# Attiny_Sumo_2020-05-22_18-39-58.net
KiCad netlist of a schematic drawn in EasyEDA
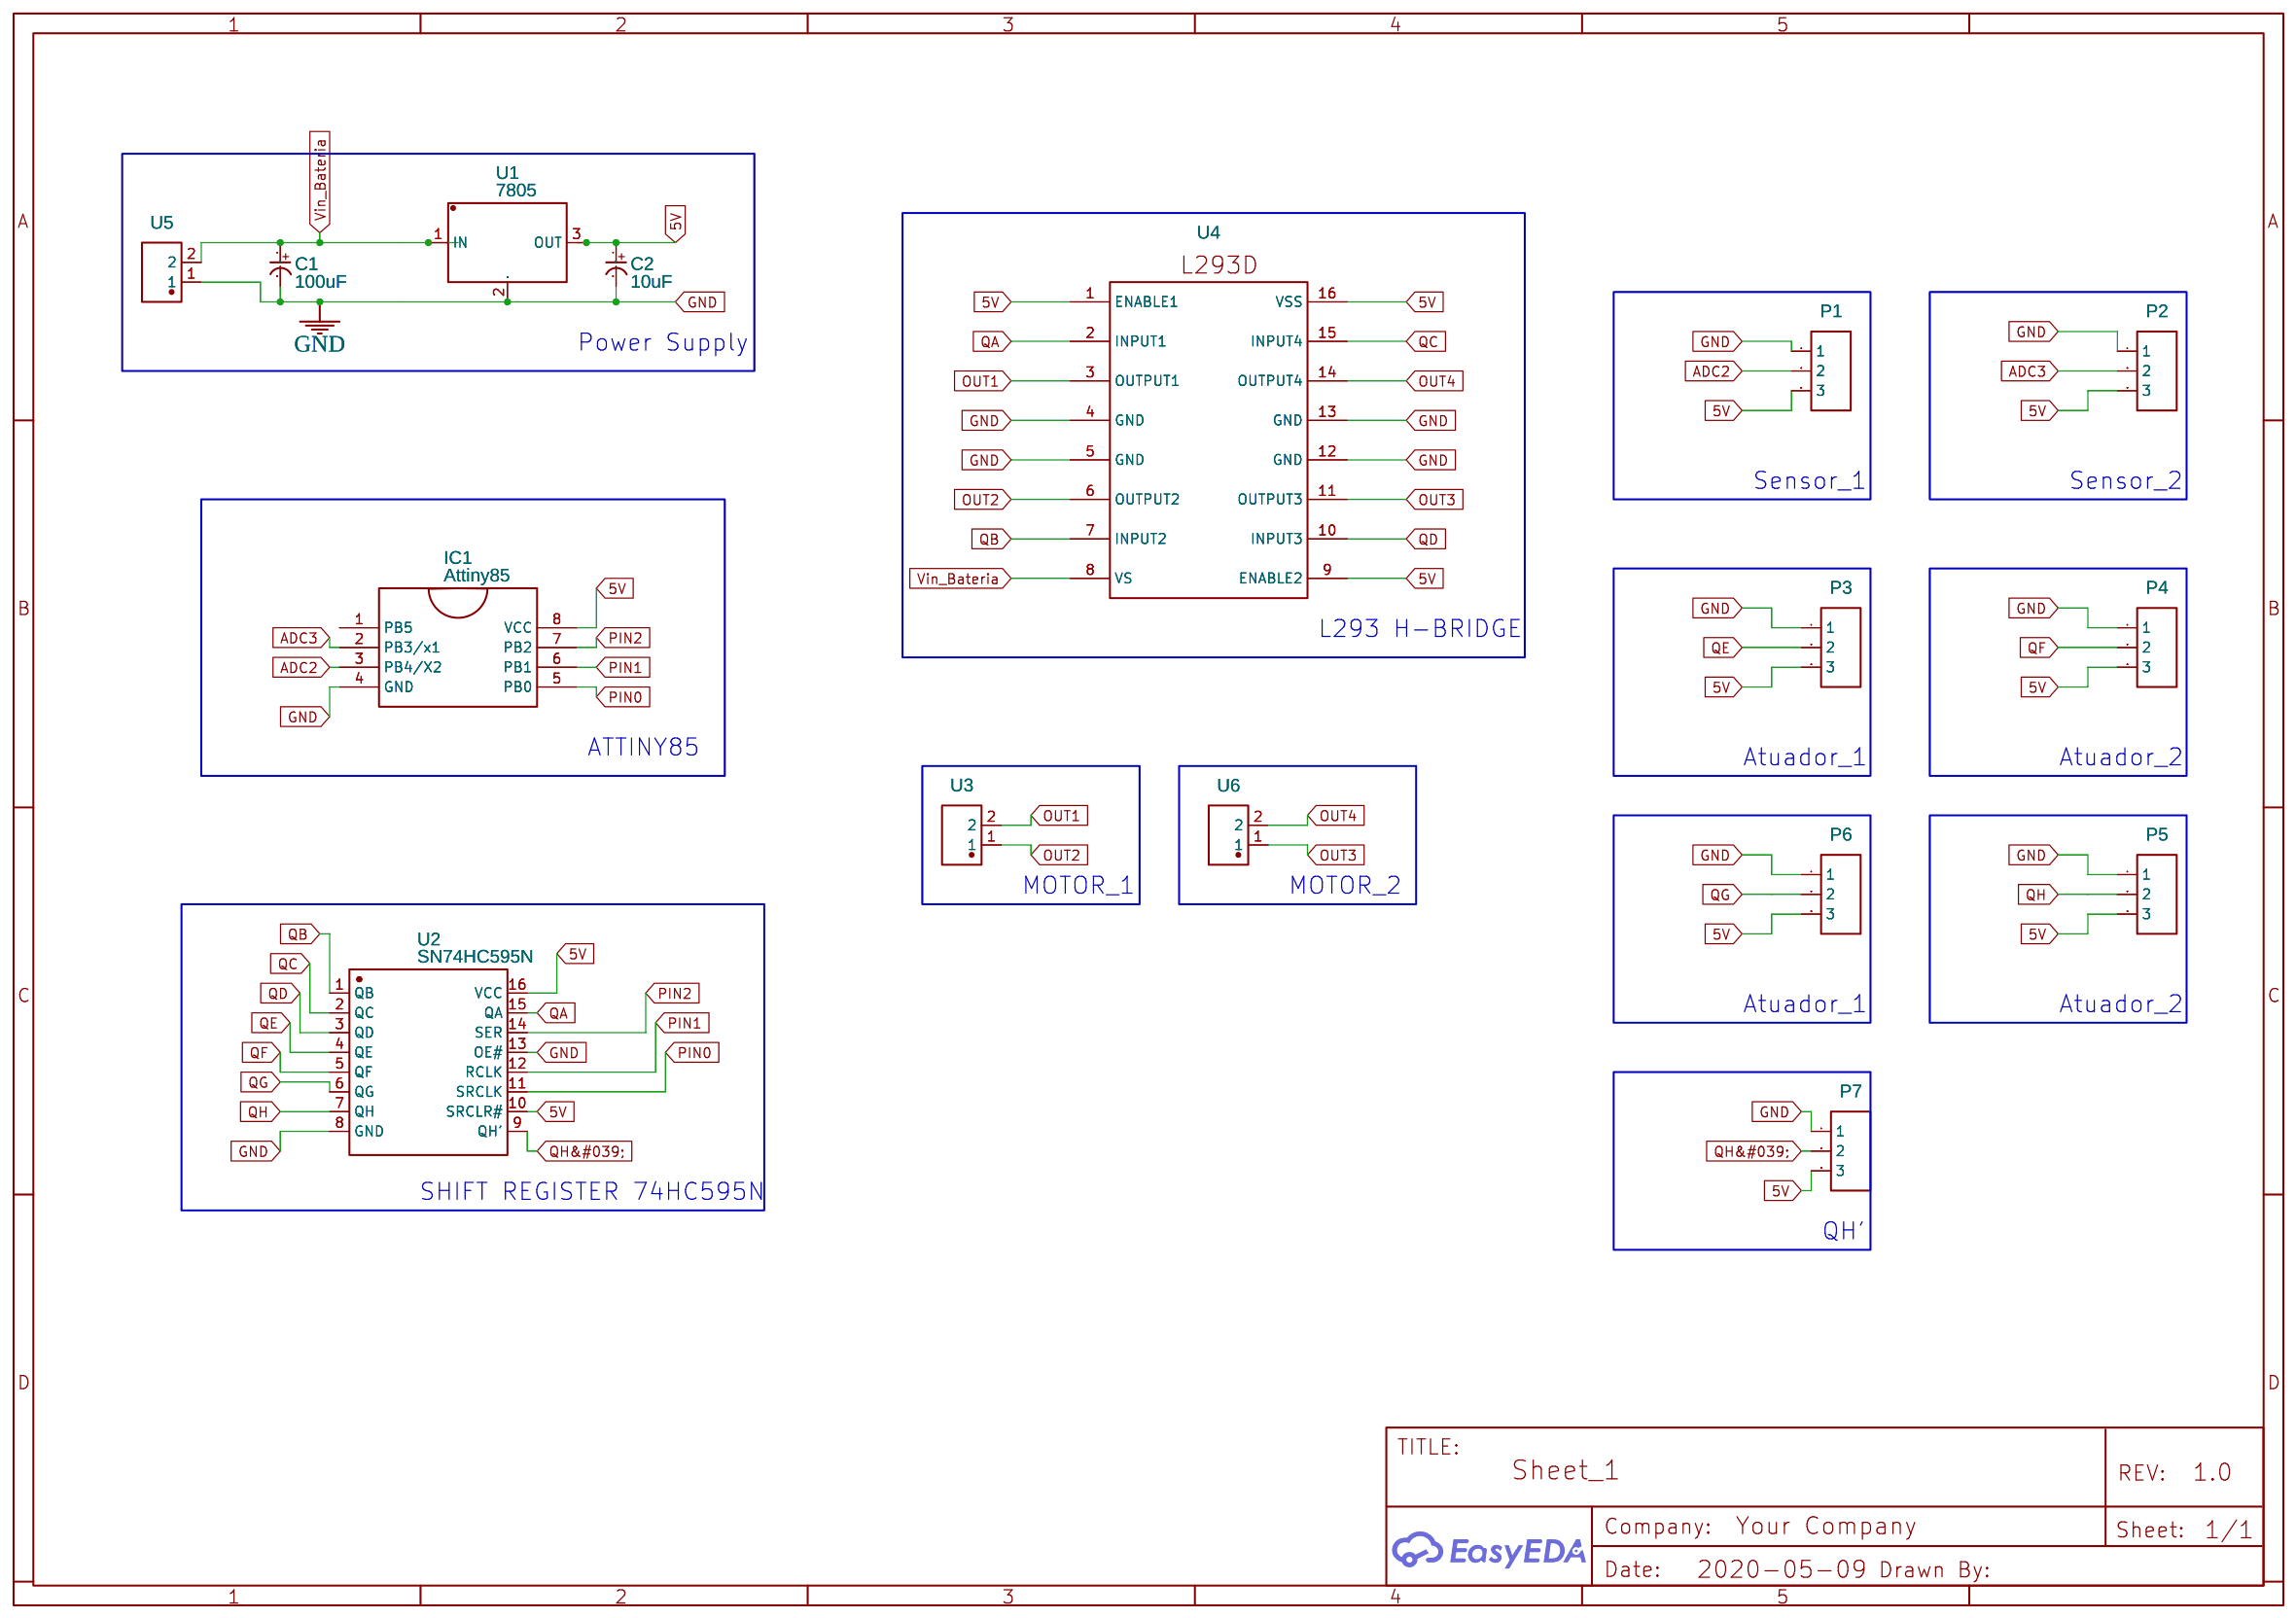
[diagram p0: schematic sheet]

(export (version "E")
  (design (tool "Eeschema 10.0.6"))
  (components
    (comp (ref "C1")
      (value "100uF")
      (fields (field (name "BOM_Manufacturer Part") "capacitor"))
      (libsource (lib "") (part "capacitor"))
    )
    (comp (ref "C2")
      (value "10uF")
      (fields (field (name "BOM_Manufacturer Part") "capacitor"))
      (libsource (lib "") (part "capacitor"))
    )
    (comp (ref "IC1") (value "Attiny85") (libsource (lib "") (part "Attiny85")))
    (comp (ref "P1")
      (value "Header-Female-2.54_1x3")
      (fields (field (name "BOM_Supplier Part") "C146243"))
      (libsource (lib "") (part "Header-Female-2.54_1x3"))
    )
    (comp (ref "P2")
      (value "Header-Female-2.54_1x3")
      (fields (field (name "BOM_Supplier Part") "C146243"))
      (libsource (lib "") (part "Header-Female-2.54_1x3"))
    )
    (comp (ref "P3")
      (value "Header-Female-2.54_1x3")
      (fields (field (name "BOM_Supplier Part") "C146243"))
      (libsource (lib "") (part "Header-Female-2.54_1x3"))
    )
    (comp (ref "P4")
      (value "Header-Female-2.54_1x3")
      (fields (field (name "BOM_Supplier Part") "C146243"))
      (libsource (lib "") (part "Header-Female-2.54_1x3"))
    )
    (comp (ref "P5")
      (value "Header-Female-2.54_1x3")
      (fields (field (name "BOM_Supplier Part") "C146243"))
      (libsource (lib "") (part "Header-Female-2.54_1x3"))
    )
    (comp (ref "P6")
      (value "Header-Female-2.54_1x3")
      (fields (field (name "BOM_Supplier Part") "C146243"))
      (libsource (lib "") (part "Header-Female-2.54_1x3"))
    )
    (comp (ref "P7")
      (value "Header-Female-2.54_1x3")
      (fields (field (name "BOM_Supplier Part") "C146243"))
      (libsource (lib "") (part "Header-Female-2.54_1x3"))
    )
    (comp (ref "U1")
      (value "7805")
      (fields (field (name "BOM_Supplier Part") "C305416"))
      (libsource (lib "") (part "7805"))
    )
    (comp (ref "U2")
      (value "SN74HC595N")
      (fields (field (name "BOM_Supplier Part") "C78711"))
      (libsource (lib "") (part "SN74HC595N"))
    )
    (comp (ref "U3")
      (value "KF396-3.96-2P")
      (fields (field (name "BOM_Supplier Part") "C474894"))
      (libsource (lib "") (part "KF396-3.96-2P"))
    )
    (comp (ref "U4")
      (value "L293D")
      (fields (field (name "BOM_Supplier Part") "C12340"))
      (libsource (lib "") (part "L293D"))
    )
    (comp (ref "U5")
      (value "KF396-3.96-2P")
      (fields (field (name "BOM_Supplier Part") "C474894"))
      (libsource (lib "") (part "KF396-3.96-2P"))
    )
    (comp (ref "U6")
      (value "KF396-3.96-2P")
      (fields (field (name "BOM_Supplier Part") "C474894"))
      (libsource (lib "") (part "KF396-3.96-2P"))
    )
  )
  (nets
    (net (code "1") (name "5V") (class "Default")
      (node (ref "C2") (pin "1") (pinfunction "1_1") (pintype "unspecified"))
      (node (ref "IC1") (pin "8") (pinfunction "VCC_8") (pintype "passive"))
      (node (ref "P1") (pin "3") (pinfunction "3_3") (pintype "input"))
      (node (ref "P2") (pin "3") (pinfunction "3_3") (pintype "input"))
      (node (ref "P3") (pin "3") (pinfunction "3_3") (pintype "input"))
      (node (ref "P4") (pin "3") (pinfunction "3_3") (pintype "input"))
      (node (ref "P5") (pin "3") (pinfunction "3_3") (pintype "input"))
      (node (ref "P6") (pin "3") (pinfunction "3_3") (pintype "input"))
      (node (ref "P7") (pin "3") (pinfunction "3_3") (pintype "input"))
      (node (ref "U1") (pin "3") (pinfunction "OUT_3") (pintype "unspecified"))
      (node (ref "U2") (pin "10") (pinfunction "SRCLR#_10") (pintype "unspecified"))
      (node (ref "U2") (pin "16") (pinfunction "VCC_16") (pintype "unspecified"))
      (node (ref "U4") (pin "1") (pinfunction "ENABLE1_1") (pintype "unspecified"))
      (node (ref "U4") (pin "16") (pinfunction "VSS_16") (pintype "unspecified"))
      (node (ref "U4") (pin "9") (pinfunction "ENABLE2_9") (pintype "unspecified"))
    )
    (net (code "2") (name "ADC2") (class "Default")
      (node (ref "IC1") (pin "3") (pinfunction "PB4/X2_3") (pintype "bidirectional"))
      (node (ref "P1") (pin "2") (pinfunction "2_2") (pintype "input"))
    )
    (net (code "3") (name "ADC3") (class "Default")
      (node (ref "IC1") (pin "2") (pinfunction "PB3/x1_2") (pintype "bidirectional"))
      (node (ref "P2") (pin "2") (pinfunction "2_2") (pintype "input"))
    )
    (net (code "4") (name "GND") (class "Default")
      (node (ref "C1") (pin "2") (pinfunction "2_2") (pintype "unspecified"))
      (node (ref "C2") (pin "2") (pinfunction "2_2") (pintype "unspecified"))
      (node (ref "IC1") (pin "4") (pinfunction "GND_4") (pintype "passive"))
      (node (ref "P1") (pin "1") (pinfunction "1_1") (pintype "input"))
      (node (ref "P2") (pin "1") (pinfunction "1_1") (pintype "input"))
      (node (ref "P3") (pin "1") (pinfunction "1_1") (pintype "input"))
      (node (ref "P4") (pin "1") (pinfunction "1_1") (pintype "input"))
      (node (ref "P5") (pin "1") (pinfunction "1_1") (pintype "input"))
      (node (ref "P6") (pin "1") (pinfunction "1_1") (pintype "input"))
      (node (ref "P7") (pin "1") (pinfunction "1_1") (pintype "input"))
      (node (ref "U1") (pin "2") (pinfunction "GND_2") (pintype "unspecified"))
      (node (ref "U2") (pin "13") (pinfunction "OE#_13") (pintype "unspecified"))
      (node (ref "U2") (pin "8") (pinfunction "GND_8") (pintype "unspecified"))
      (node (ref "U4") (pin "12") (pinfunction "GND_12") (pintype "unspecified"))
      (node (ref "U4") (pin "13") (pinfunction "GND_13") (pintype "unspecified"))
      (node (ref "U4") (pin "4") (pinfunction "GND_4") (pintype "unspecified"))
      (node (ref "U4") (pin "5") (pinfunction "GND_5") (pintype "unspecified"))
      (node (ref "U5") (pin "1") (pinfunction "1_1") (pintype "unspecified"))
    )
    (net (code "5") (name "OUT1") (class "Default")
      (node (ref "U3") (pin "2") (pinfunction "2_2") (pintype "unspecified"))
      (node (ref "U4") (pin "3") (pinfunction "OUTPUT1_3") (pintype "unspecified"))
    )
    (net (code "6") (name "OUT2") (class "Default")
      (node (ref "U3") (pin "1") (pinfunction "1_1") (pintype "unspecified"))
      (node (ref "U4") (pin "6") (pinfunction "OUTPUT2_6") (pintype "unspecified"))
    )
    (net (code "7") (name "OUT3") (class "Default")
      (node (ref "U4") (pin "11") (pinfunction "OUTPUT3_11") (pintype "unspecified"))
      (node (ref "U6") (pin "1") (pinfunction "1_1") (pintype "unspecified"))
    )
    (net (code "8") (name "OUT4") (class "Default")
      (node (ref "U4") (pin "14") (pinfunction "OUTPUT4_14") (pintype "unspecified"))
      (node (ref "U6") (pin "2") (pinfunction "2_2") (pintype "unspecified"))
    )
    (net (code "9") (name "PIN0") (class "Default")
      (node (ref "IC1") (pin "5") (pinfunction "PB0_5") (pintype "bidirectional"))
      (node (ref "U2") (pin "11") (pinfunction "SRCLK_11") (pintype "unspecified"))
    )
    (net (code "10") (name "PIN1") (class "Default")
      (node (ref "IC1") (pin "6") (pinfunction "PB1_6") (pintype "bidirectional"))
      (node (ref "U2") (pin "12") (pinfunction "RCLK_12") (pintype "unspecified"))
    )
    (net (code "11") (name "PIN2") (class "Default")
      (node (ref "IC1") (pin "7") (pinfunction "PB2_7") (pintype "bidirectional"))
      (node (ref "U2") (pin "14") (pinfunction "SER_14") (pintype "unspecified"))
    )
    (net (code "12") (name "QA") (class "Default")
      (node (ref "U2") (pin "15") (pinfunction "QA_15") (pintype "unspecified"))
      (node (ref "U4") (pin "2") (pinfunction "INPUT1_2") (pintype "unspecified"))
    )
    (net (code "13") (name "QB") (class "Default")
      (node (ref "U2") (pin "1") (pinfunction "QB_1") (pintype "unspecified"))
      (node (ref "U4") (pin "7") (pinfunction "INPUT2_7") (pintype "unspecified"))
    )
    (net (code "14") (name "QC") (class "Default")
      (node (ref "U2") (pin "2") (pinfunction "QC_2") (pintype "unspecified"))
      (node (ref "U4") (pin "15") (pinfunction "INPUT4_15") (pintype "unspecified"))
    )
    (net (code "15") (name "QD") (class "Default")
      (node (ref "U2") (pin "3") (pinfunction "QD_3") (pintype "unspecified"))
      (node (ref "U4") (pin "10") (pinfunction "INPUT3_10") (pintype "unspecified"))
    )
    (net (code "16") (name "QE") (class "Default")
      (node (ref "P3") (pin "2") (pinfunction "2_2") (pintype "input"))
      (node (ref "U2") (pin "4") (pinfunction "QE_4") (pintype "unspecified"))
    )
    (net (code "17") (name "QF") (class "Default")
      (node (ref "P4") (pin "2") (pinfunction "2_2") (pintype "input"))
      (node (ref "U2") (pin "5") (pinfunction "QF_5") (pintype "unspecified"))
    )
    (net (code "18") (name "QG") (class "Default")
      (node (ref "P6") (pin "2") (pinfunction "2_2") (pintype "input"))
      (node (ref "U2") (pin "6") (pinfunction "QG_6") (pintype "unspecified"))
    )
    (net (code "19") (name "QH") (class "Default")
      (node (ref "P5") (pin "2") (pinfunction "2_2") (pintype "input"))
      (node (ref "U2") (pin "7") (pinfunction "QH_7") (pintype "unspecified"))
    )
    (net (code "20") (name "QH&#039;") (class "Default")
      (node (ref "P7") (pin "2") (pinfunction "2_2") (pintype "input"))
      (node (ref "U2") (pin "9") (pinfunction "QH'_9") (pintype "unspecified"))
    )
    (net (code "21") (name "Vin_Bateria") (class "Default")
      (node (ref "C1") (pin "1") (pinfunction "1_1") (pintype "unspecified"))
      (node (ref "U1") (pin "1") (pinfunction "IN_1") (pintype "unspecified"))
      (node (ref "U4") (pin "8") (pinfunction "VS_8") (pintype "unspecified"))
      (node (ref "U5") (pin "2") (pinfunction "2_2") (pintype "unspecified"))
    )
    (net (code "22") (name "unconnected-(IC1-PB5-Pad1)") (class "Default")
      (node (ref "IC1") (pin "1") (pinfunction "PB5_1") (pintype "bidirectional"))
    )
  )
)
